# ESP8266_12E_1_5.net
KiCad netlist of a schematic drawn in EAGLE
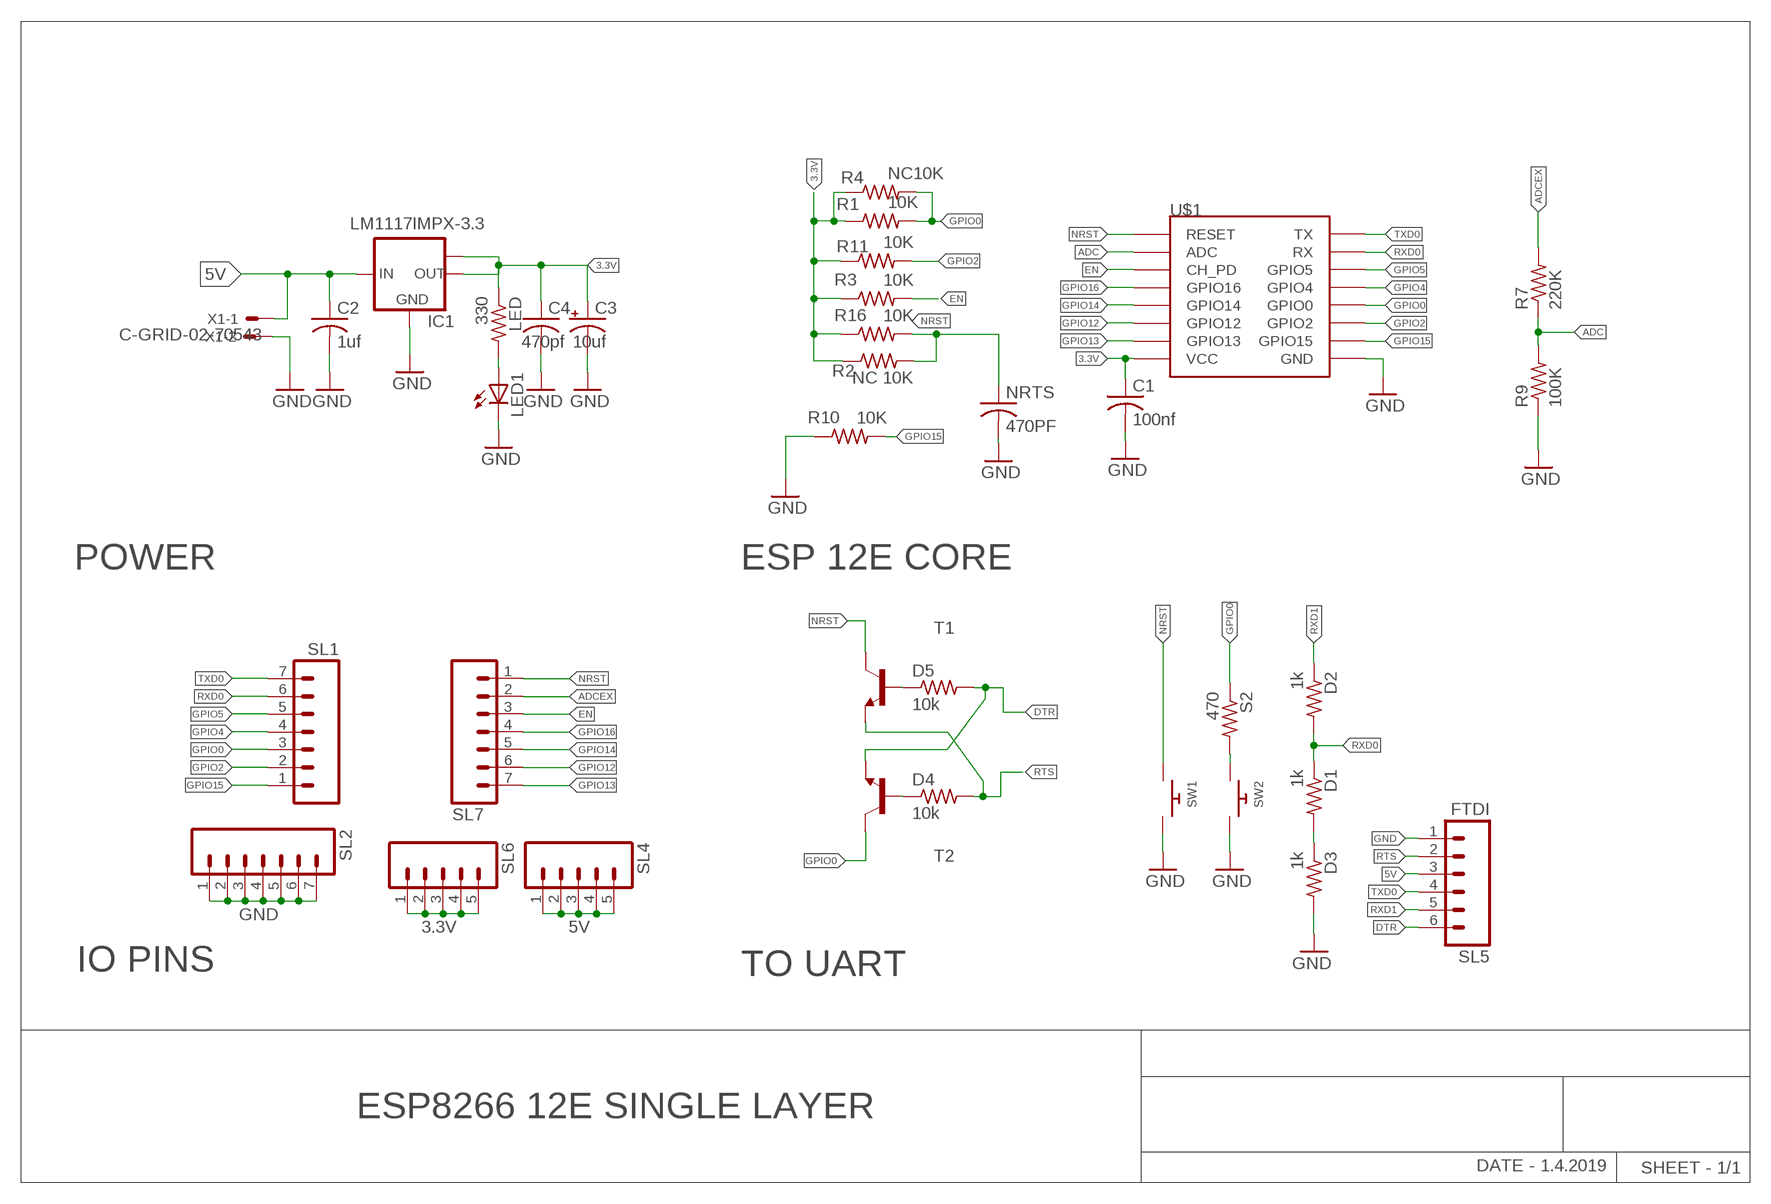
[diagram p0: schematic, sheet 1]

(export (version "E")
  (design (tool "Eeschema 10.0.6"))
  (components
    (comp (ref "C1")
      (value "100nf")
      (footprint "eagle-import:C050-025X075")
      (libsource (lib "eagle-import") (part "resistor_348_C-US050-025X075"))
    )
    (comp (ref "C2")
      (value "1uf")
      (footprint "eagle-import:C050-030X075")
      (libsource (lib "eagle-import") (part "C-US050-030X075"))
    )
    (comp (ref "C3")
      (value "10uf")
      (footprint "eagle-import:E2,5-5")
      (libsource (lib "eagle-import") (part "CPOL-USE2.5-5"))
    )
    (comp (ref "C4")
      (value "470pf")
      (footprint "eagle-import:C050-025X075")
      (libsource (lib "eagle-import") (part "resistor_348_C-US050-025X075"))
    )
    (comp (ref "D1")
      (value "1k")
      (footprint "eagle-import:0309_10")
      (libsource (lib "eagle-import") (part "R-US_0309/10"))
    )
    (comp (ref "D2")
      (value "1k")
      (footprint "eagle-import:0309_10")
      (libsource (lib "eagle-import") (part "R-US_0309/10"))
    )
    (comp (ref "D3")
      (value "1k")
      (footprint "eagle-import:0309_10")
      (libsource (lib "eagle-import") (part "R-US_0309/10"))
    )
    (comp (ref "D4")
      (value "10k")
      (footprint "eagle-import:0309_10")
      (libsource (lib "eagle-import") (part "R-US_0309/10"))
    )
    (comp (ref "D5")
      (value "10k")
      (footprint "eagle-import:0309_10")
      (libsource (lib "eagle-import") (part "R-US_0309/10"))
    )
    (comp (ref "IC1")
      (value "LM1117IMPX-3.3")
      (footprint "eagle-import:SOT223")
      (libsource (lib "eagle-import") (part "LM1117IMPX-3.3"))
    )
    (comp (ref "LED")
      (value "330")
      (footprint "eagle-import:0309_10")
      (libsource (lib "eagle-import") (part "R-US_0309/10"))
    )
    (comp (ref "LED1")
      (value "LED3MM")
      (footprint "eagle-import:LED3MM")
      (libsource (lib "eagle-import") (part "LED3MM"))
    )
    (comp (ref "NRTS")
      (value "470PF")
      (footprint "eagle-import:C050-025X075")
      (libsource (lib "eagle-import") (part "resistor_348_C-US050-025X075"))
    )
    (comp (ref "R1")
      (value "10K")
      (footprint "eagle-import:0207_7")
      (libsource (lib "eagle-import") (part "R-US_0207/7"))
    )
    (comp (ref "R2")
      (value "NC 10K")
      (footprint "eagle-import:M1206")
      (libsource (lib "eagle-import") (part "R-US_M1206"))
    )
    (comp (ref "R3")
      (value "10K")
      (footprint "eagle-import:0207_7")
      (libsource (lib "eagle-import") (part "R-US_0207/7"))
    )
    (comp (ref "R4")
      (value "NC10K")
      (footprint "eagle-import:0207_7")
      (libsource (lib "eagle-import") (part "R-US_0207/7"))
    )
    (comp (ref "R7")
      (value "220K")
      (footprint "eagle-import:0309_10")
      (libsource (lib "eagle-import") (part "R-US_0309/10"))
    )
    (comp (ref "R9")
      (value "100K")
      (footprint "eagle-import:0309_10")
      (libsource (lib "eagle-import") (part "R-US_0309/10"))
    )
    (comp (ref "R10")
      (value "10K")
      (footprint "eagle-import:0207_7")
      (libsource (lib "eagle-import") (part "R-US_0207/7"))
    )
    (comp (ref "R11")
      (value "10K")
      (footprint "eagle-import:0207_7")
      (libsource (lib "eagle-import") (part "R-US_0207/7"))
    )
    (comp (ref "R16")
      (value "10K")
      (footprint "eagle-import:0207_7")
      (libsource (lib "eagle-import") (part "R-US_0207/7"))
    )
    (comp (ref "S2")
      (value "470")
      (footprint "eagle-import:0309_10")
      (libsource (lib "eagle-import") (part "R-US_0309/10"))
    )
    (comp (ref "SL1")
      (value "M07")
      (footprint "eagle-import:07P")
      (libsource (lib "eagle-import") (part "M07"))
    )
    (comp (ref "SL2")
      (value "M07")
      (footprint "eagle-import:07P")
      (libsource (lib "eagle-import") (part "M07"))
    )
    (comp (ref "SL4")
      (value "M05")
      (footprint "eagle-import:05P")
      (libsource (lib "eagle-import") (part "M05"))
    )
    (comp (ref "SL5")
      (value "FTDI")
      (footprint "eagle-import:06P")
      (libsource (lib "eagle-import") (part "M06"))
    )
    (comp (ref "SL6")
      (value "M05")
      (footprint "eagle-import:05P")
      (libsource (lib "eagle-import") (part "M05"))
    )
    (comp (ref "SL7")
      (value "M07")
      (footprint "eagle-import:07P")
      (libsource (lib "eagle-import") (part "M07"))
    )
    (comp (ref "SW1")
      (value "SWITCH_PUSHBUTTONEVQ")
      (footprint "eagle-import:0204_5")
      (libsource (lib "eagle-import") (part "SWITCH_PUSHBUTTONEVQ"))
    )
    (comp (ref "SW2")
      (value "SWITCH_PUSHBUTTONEVQ")
      (footprint "eagle-import:0204_5")
      (libsource (lib "eagle-import") (part "SWITCH_PUSHBUTTONEVQ"))
    )
    (comp (ref "T1")
      (value "2N2222")
      (footprint "eagle-import:TO92-EBC-OVAL")
      (libsource (lib "eagle-import") (part "2N2222"))
    )
    (comp (ref "T2")
      (value "2N2222")
      (footprint "eagle-import:TO92-EBC-OVAL")
      (libsource (lib "eagle-import") (part "2N2222"))
    )
    (comp (ref "U$1")
      (value "ESP8266")
      (footprint "eagle-import:ESP8266MIRROR")
      (libsource (lib "eagle-import") (part "ESP8266"))
    )
    (comp (ref "X1")
      (value "C-GRID-02-70543")
      (footprint "eagle-import:70543-02")
      (fields (field (name "MF") "MOLEX"))
      (libsource (lib "eagle-import") (part "C-GRID-02-70543"))
    )
  )
  (nets
    (net (code "1") (name "3.3V") (class "Default")
      (node (ref "C1") (pin "1") (pinfunction "1_1") (pintype "passive"))
      (node (ref "C3") (pin "+") (pinfunction "+_+") (pintype "passive"))
      (node (ref "C4") (pin "1") (pinfunction "1_1") (pintype "passive"))
      (node (ref "IC1") (pin "2") (pinfunction "OUT_2") (pintype "passive"))
      (node (ref "IC1") (pin "TAB") (pinfunction "OUT1_TAB") (pintype "passive"))
      (node (ref "LED") (pin "1") (pinfunction "1_1") (pintype "passive"))
      (node (ref "R1") (pin "1") (pinfunction "1_1") (pintype "passive"))
      (node (ref "R11") (pin "1") (pinfunction "1_1") (pintype "passive"))
      (node (ref "R16") (pin "1") (pinfunction "1_1") (pintype "passive"))
      (node (ref "R2") (pin "1") (pinfunction "1_1") (pintype "passive"))
      (node (ref "R3") (pin "1") (pinfunction "1_1") (pintype "passive"))
      (node (ref "R4") (pin "1") (pinfunction "1_1") (pintype "passive"))
      (node (ref "SL6") (pin "1") (pinfunction "1_1") (pintype "passive"))
      (node (ref "SL6") (pin "2") (pinfunction "2_2") (pintype "passive"))
      (node (ref "SL6") (pin "3") (pinfunction "3_3") (pintype "passive"))
      (node (ref "SL6") (pin "4") (pinfunction "4_4") (pintype "passive"))
      (node (ref "SL6") (pin "5") (pinfunction "5_5") (pintype "passive"))
      (node (ref "U$1") (pin "VCC") (pinfunction "VCC_VCC") (pintype "bidirectional"))
    )
    (net (code "2") (name "5V") (class "Default")
      (node (ref "C2") (pin "1") (pinfunction "1_1") (pintype "passive"))
      (node (ref "IC1") (pin "3") (pinfunction "IN_3") (pintype "input"))
      (node (ref "SL4") (pin "1") (pinfunction "1_1") (pintype "passive"))
      (node (ref "SL4") (pin "2") (pinfunction "2_2") (pintype "passive"))
      (node (ref "SL4") (pin "3") (pinfunction "3_3") (pintype "passive"))
      (node (ref "SL4") (pin "4") (pinfunction "4_4") (pintype "passive"))
      (node (ref "SL4") (pin "5") (pinfunction "5_5") (pintype "passive"))
      (node (ref "SL5") (pin "3") (pinfunction "3_3") (pintype "passive"))
      (node (ref "X1") (pin "1") (pinfunction "S_1") (pintype "passive"))
    )
    (net (code "3") (name "ADC") (class "Default")
      (node (ref "R7") (pin "1") (pinfunction "1_1") (pintype "passive"))
      (node (ref "R9") (pin "2") (pinfunction "2_2") (pintype "passive"))
      (node (ref "U$1") (pin "ADC") (pinfunction "ADC_ADC") (pintype "bidirectional"))
    )
    (net (code "4") (name "ADCEX") (class "Default")
      (node (ref "R7") (pin "2") (pinfunction "2_2") (pintype "passive"))
      (node (ref "SL7") (pin "2") (pinfunction "2_2") (pintype "passive"))
    )
    (net (code "5") (name "DTR") (class "Default")
      (node (ref "D5") (pin "2") (pinfunction "2_2") (pintype "passive"))
      (node (ref "SL5") (pin "6") (pinfunction "6_6") (pintype "passive"))
      (node (ref "T2") (pin "E") (pinfunction "E_E") (pintype "passive"))
    )
    (net (code "6") (name "EN") (class "Default")
      (node (ref "R3") (pin "2") (pinfunction "2_2") (pintype "passive"))
      (node (ref "SL7") (pin "3") (pinfunction "3_3") (pintype "passive"))
      (node (ref "U$1") (pin "EN") (pinfunction "CH_PD_EN") (pintype "bidirectional"))
    )
    (net (code "7") (name "GND") (class "Default")
      (node (ref "C1") (pin "2") (pinfunction "2_2") (pintype "passive"))
      (node (ref "C2") (pin "2") (pinfunction "2_2") (pintype "passive"))
      (node (ref "C3") (pin "-") (pinfunction "-_-") (pintype "passive"))
      (node (ref "C4") (pin "2") (pinfunction "2_2") (pintype "passive"))
      (node (ref "D3") (pin "2") (pinfunction "2_2") (pintype "passive"))
      (node (ref "IC1") (pin "1") (pinfunction "GND_1") (pintype "input"))
      (node (ref "LED1") (pin "K") (pinfunction "C_K") (pintype "passive"))
      (node (ref "NRTS") (pin "2") (pinfunction "2_2") (pintype "passive"))
      (node (ref "R10") (pin "1") (pinfunction "1_1") (pintype "passive"))
      (node (ref "R9") (pin "1") (pinfunction "1_1") (pintype "passive"))
      (node (ref "SL2") (pin "1") (pinfunction "1_1") (pintype "passive"))
      (node (ref "SL2") (pin "2") (pinfunction "2_2") (pintype "passive"))
      (node (ref "SL2") (pin "3") (pinfunction "3_3") (pintype "passive"))
      (node (ref "SL2") (pin "4") (pinfunction "4_4") (pintype "passive"))
      (node (ref "SL2") (pin "5") (pinfunction "5_5") (pintype "passive"))
      (node (ref "SL2") (pin "6") (pinfunction "6_6") (pintype "passive"))
      (node (ref "SL2") (pin "7") (pinfunction "7_7") (pintype "passive"))
      (node (ref "SL5") (pin "1") (pinfunction "1_1") (pintype "passive"))
      (node (ref "SW1") (pin "2") (pinfunction "P$2_2") (pintype "passive"))
      (node (ref "SW2") (pin "2") (pinfunction "P$2_2") (pintype "passive"))
      (node (ref "U$1") (pin "GND") (pinfunction "GND_GND") (pintype "bidirectional"))
      (node (ref "X1") (pin "2") (pinfunction "S_2") (pintype "passive"))
    )
    (net (code "8") (name "GPIO0") (class "Default")
      (node (ref "R1") (pin "2") (pinfunction "2_2") (pintype "passive"))
      (node (ref "R4") (pin "2") (pinfunction "2_2") (pintype "passive"))
      (node (ref "S2") (pin "1") (pinfunction "1_1") (pintype "passive"))
      (node (ref "SL1") (pin "3") (pinfunction "3_3") (pintype "passive"))
      (node (ref "T2") (pin "C") (pinfunction "C_C") (pintype "passive"))
      (node (ref "U$1") (pin "0") (pinfunction "GPIO0_0") (pintype "bidirectional"))
    )
    (net (code "9") (name "GPIO2") (class "Default")
      (node (ref "R11") (pin "2") (pinfunction "2_2") (pintype "passive"))
      (node (ref "SL1") (pin "2") (pinfunction "2_2") (pintype "passive"))
      (node (ref "U$1") (pin "2") (pinfunction "GPIO2_2") (pintype "bidirectional"))
    )
    (net (code "10") (name "GPIO4") (class "Default")
      (node (ref "SL1") (pin "4") (pinfunction "4_4") (pintype "passive"))
      (node (ref "U$1") (pin "4") (pinfunction "GPIO4_4") (pintype "bidirectional"))
    )
    (net (code "11") (name "GPIO5") (class "Default")
      (node (ref "SL1") (pin "5") (pinfunction "5_5") (pintype "passive"))
      (node (ref "U$1") (pin "5") (pinfunction "GPIO5_5") (pintype "bidirectional"))
    )
    (net (code "12") (name "GPIO12") (class "Default")
      (node (ref "SL7") (pin "6") (pinfunction "6_6") (pintype "passive"))
      (node (ref "U$1") (pin "12") (pinfunction "GPIO12_12") (pintype "bidirectional"))
    )
    (net (code "13") (name "GPIO13") (class "Default")
      (node (ref "SL7") (pin "7") (pinfunction "7_7") (pintype "passive"))
      (node (ref "U$1") (pin "13") (pinfunction "GPIO13_13") (pintype "bidirectional"))
    )
    (net (code "14") (name "GPIO14") (class "Default")
      (node (ref "SL7") (pin "5") (pinfunction "5_5") (pintype "passive"))
      (node (ref "U$1") (pin "14") (pinfunction "GPIO14_14") (pintype "bidirectional"))
    )
    (net (code "15") (name "GPIO15") (class "Default")
      (node (ref "R10") (pin "2") (pinfunction "2_2") (pintype "passive"))
      (node (ref "SL1") (pin "1") (pinfunction "1_1") (pintype "passive"))
      (node (ref "U$1") (pin "15") (pinfunction "GPIO15_15") (pintype "bidirectional"))
    )
    (net (code "16") (name "GPIO16") (class "Default")
      (node (ref "SL7") (pin "4") (pinfunction "4_4") (pintype "passive"))
      (node (ref "U$1") (pin "16") (pinfunction "GPIO16_16") (pintype "bidirectional"))
    )
    (net (code "17") (name "NRST") (class "Default")
      (node (ref "NRTS") (pin "1") (pinfunction "1_1") (pintype "passive"))
      (node (ref "R16") (pin "2") (pinfunction "2_2") (pintype "passive"))
      (node (ref "R2") (pin "2") (pinfunction "2_2") (pintype "passive"))
      (node (ref "SL7") (pin "1") (pinfunction "1_1") (pintype "passive"))
      (node (ref "SW1") (pin "1") (pinfunction "P$1_1") (pintype "passive"))
      (node (ref "T1") (pin "C") (pinfunction "C_C") (pintype "passive"))
      (node (ref "U$1") (pin "RST") (pinfunction "RESET_RST") (pintype "bidirectional"))
    )
    (net (code "18") (name "Net-(D1-Pad2)") (class "Default")
      (node (ref "D1") (pin "2") (pinfunction "2_2") (pintype "passive"))
      (node (ref "D3") (pin "1") (pinfunction "1_1") (pintype "passive"))
    )
    (net (code "19") (name "Net-(D4-Pad1)") (class "Default")
      (node (ref "D4") (pin "1") (pinfunction "1_1") (pintype "passive"))
      (node (ref "T2") (pin "B") (pinfunction "B_B") (pintype "passive"))
    )
    (net (code "20") (name "Net-(D5-Pad1)") (class "Default")
      (node (ref "D5") (pin "1") (pinfunction "1_1") (pintype "passive"))
      (node (ref "T1") (pin "B") (pinfunction "B_B") (pintype "passive"))
    )
    (net (code "21") (name "Net-(LED-Pad2)") (class "Default")
      (node (ref "LED") (pin "2") (pinfunction "2_2") (pintype "passive"))
      (node (ref "LED1") (pin "A") (pinfunction "A_A") (pintype "passive"))
    )
    (net (code "22") (name "Net-(SW2-P$1)") (class "Default")
      (node (ref "S2") (pin "2") (pinfunction "2_2") (pintype "passive"))
      (node (ref "SW2") (pin "1") (pinfunction "P$1_1") (pintype "passive"))
    )
    (net (code "23") (name "RTS") (class "Default")
      (node (ref "D4") (pin "2") (pinfunction "2_2") (pintype "passive"))
      (node (ref "SL5") (pin "2") (pinfunction "2_2") (pintype "passive"))
      (node (ref "T1") (pin "E") (pinfunction "E_E") (pintype "passive"))
    )
    (net (code "24") (name "RXD0") (class "Default")
      (node (ref "D1") (pin "1") (pinfunction "1_1") (pintype "passive"))
      (node (ref "D2") (pin "2") (pinfunction "2_2") (pintype "passive"))
      (node (ref "SL1") (pin "6") (pinfunction "6_6") (pintype "passive"))
      (node (ref "U$1") (pin "RX") (pinfunction "RX_RX") (pintype "bidirectional"))
    )
    (net (code "25") (name "RXD1") (class "Default")
      (node (ref "D2") (pin "1") (pinfunction "1_1") (pintype "passive"))
      (node (ref "SL5") (pin "5") (pinfunction "5_5") (pintype "passive"))
    )
    (net (code "26") (name "TXD0") (class "Default")
      (node (ref "SL1") (pin "7") (pinfunction "7_7") (pintype "passive"))
      (node (ref "SL5") (pin "4") (pinfunction "4_4") (pintype "passive"))
      (node (ref "U$1") (pin "TX") (pinfunction "TX_TX") (pintype "bidirectional"))
    )
  )
)
